# h-bridge-gate-driver-buk.net
KiCad netlist of a schematic drawn in EAGLE
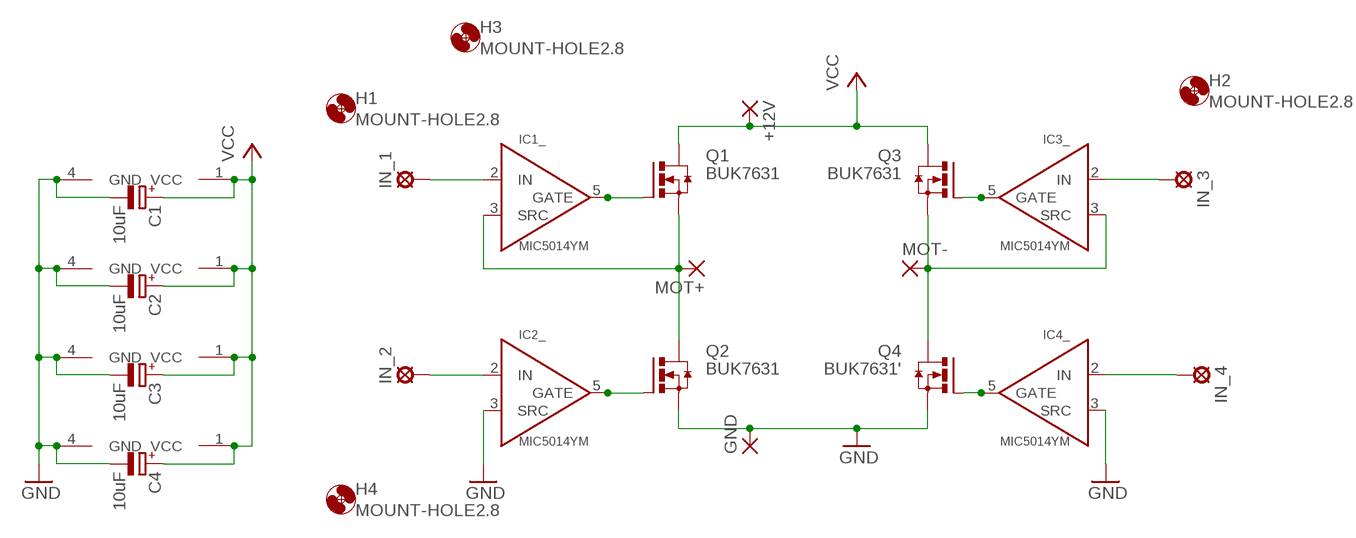
[diagram p0: schematic, sheet 1]

(export (version "E")
  (design (tool "Eeschema 10.0.6"))
  (components
    (comp (ref "+12V")
      (value "WIREPAD4,16O1,6")
      (footprint "eagle-import:4,16O1,6")
      (libsource (lib "eagle-import") (part "WIREPAD4,16O1,6"))
    )
    (comp (ref "C1")
      (value "10uF")
      (footprint "eagle-import:UD-4X5,8_NICHICON")
      (libsource (lib "eagle-import") (part "CPOL-EUUD-4X5,8"))
    )
    (comp (ref "C2")
      (value "10uF")
      (footprint "eagle-import:UD-4X5,8_NICHICON")
      (libsource (lib "eagle-import") (part "CPOL-EUUD-4X5,8"))
    )
    (comp (ref "C3")
      (value "10uF")
      (footprint "eagle-import:UD-4X5,8_NICHICON")
      (libsource (lib "eagle-import") (part "CPOL-EUUD-4X5,8"))
    )
    (comp (ref "C4")
      (value "10uF")
      (footprint "eagle-import:UD-4X5,8_NICHICON")
      (libsource (lib "eagle-import") (part "CPOL-EUUD-4X5,8"))
    )
    (comp (ref "GND")
      (value "WIREPAD4,16O1,6")
      (footprint "eagle-import:4,16O1,6")
      (libsource (lib "eagle-import") (part "WIREPAD4,16O1,6"))
    )
    (comp (ref "H1")
      (value "MOUNT-HOLE2.8")
      (footprint "eagle-import:2,8")
      (libsource (lib "eagle-import") (part "MOUNT-HOLE2.8"))
    )
    (comp (ref "H2")
      (value "MOUNT-HOLE2.8")
      (footprint "eagle-import:2,8")
      (libsource (lib "eagle-import") (part "MOUNT-HOLE2.8"))
    )
    (comp (ref "H3")
      (value "MOUNT-HOLE2.8")
      (footprint "eagle-import:2,8")
      (libsource (lib "eagle-import") (part "MOUNT-HOLE2.8"))
    )
    (comp (ref "H4")
      (value "MOUNT-HOLE2.8")
      (footprint "eagle-import:2,8")
      (libsource (lib "eagle-import") (part "MOUNT-HOLE2.8"))
    )
    (comp (ref "IC1")
      (value "MIC5014YM")
      (footprint "eagle-import:SO8")
      (libsource (lib "eagle-import") (part "MIC5014YM"))
    )
    (comp (ref "IC2")
      (value "MIC5014YM")
      (footprint "eagle-import:SO8")
      (libsource (lib "eagle-import") (part "MIC5014YM"))
    )
    (comp (ref "IC3")
      (value "MIC5014YM")
      (footprint "eagle-import:SO8")
      (libsource (lib "eagle-import") (part "MIC5014YM"))
    )
    (comp (ref "IC4")
      (value "MIC5014YM")
      (footprint "eagle-import:SO8")
      (libsource (lib "eagle-import") (part "MIC5014YM"))
    )
    (comp (ref "IN_1")
      (value "LSP11")
      (footprint "eagle-import:LSP11")
      (libsource (lib "eagle-import") (part "LSP11"))
    )
    (comp (ref "IN_2")
      (value "LSP11")
      (footprint "eagle-import:LSP11")
      (libsource (lib "eagle-import") (part "LSP11"))
    )
    (comp (ref "IN_3")
      (value "LSP11")
      (footprint "eagle-import:LSP11")
      (libsource (lib "eagle-import") (part "LSP11"))
    )
    (comp (ref "IN_4")
      (value "LSP11")
      (footprint "eagle-import:LSP11")
      (libsource (lib "eagle-import") (part "LSP11"))
    )
    (comp (ref "MOT+")
      (value "WIREPAD4,16O1,6")
      (footprint "eagle-import:4,16O1,6")
      (libsource (lib "eagle-import") (part "WIREPAD4,16O1,6"))
    )
    (comp (ref "MOT-")
      (value "WIREPAD4,16O1,6")
      (footprint "eagle-import:4,16O1,6")
      (libsource (lib "eagle-import") (part "WIREPAD4,16O1,6"))
    )
    (comp (ref "Q1")
      (value "BUK7631")
      (footprint "eagle-import:D2PAK_TO263")
      (libsource (lib "eagle-import") (part "BUK7631-100EBUK7631-100E"))
    )
    (comp (ref "Q2")
      (value "BUK7631")
      (footprint "eagle-import:D2PAK_TO263")
      (libsource (lib "eagle-import") (part "BUK7631-100EBUK7631-100E"))
    )
    (comp (ref "Q3")
      (value "BUK7631")
      (footprint "eagle-import:D2PAK_TO263")
      (libsource (lib "eagle-import") (part "BUK7631-100EBUK7631-100E"))
    )
    (comp (ref "Q4")
      (value "BUK7631'")
      (footprint "eagle-import:D2PAK_TO263")
      (libsource (lib "eagle-import") (part "BUK7631-100EBUK7631-100E"))
    )
  )
  (nets
    (net (code "1") (name "GND") (class "Default")
      (node (ref "C1") (pin "-") (pinfunction "-_-") (pintype "passive"))
      (node (ref "C2") (pin "-") (pinfunction "-_-") (pintype "passive"))
      (node (ref "C3") (pin "-") (pinfunction "-_-") (pintype "passive"))
      (node (ref "C4") (pin "-") (pinfunction "-_-") (pintype "passive"))
      (node (ref "GND") (pin "1") (pinfunction "P_1") (pintype "passive"))
      (node (ref "IC1") (pin "4") (pinfunction "GND_4") (pintype "power_in"))
      (node (ref "IC2") (pin "3") (pinfunction "SRC_3") (pintype "passive"))
      (node (ref "IC2") (pin "4") (pinfunction "GND_4") (pintype "power_in"))
      (node (ref "IC3") (pin "4") (pinfunction "GND_4") (pintype "power_in"))
      (node (ref "IC4") (pin "3") (pinfunction "SRC_3") (pintype "passive"))
      (node (ref "IC4") (pin "4") (pinfunction "GND_4") (pintype "power_in"))
      (node (ref "Q2") (pin "3") (pinfunction "S_3") (pintype "passive"))
      (node (ref "Q4") (pin "3") (pinfunction "S_3") (pintype "passive"))
    )
    (net (code "2") (name "Net-(IC1B-GATE)") (class "Default")
      (node (ref "IC1") (pin "5") (pinfunction "GATE_5") (pintype "passive"))
      (node (ref "Q1") (pin "1") (pinfunction "G_1") (pintype "passive"))
    )
    (net (code "3") (name "Net-(IC1B-IN)") (class "Default")
      (node (ref "IC1") (pin "2") (pinfunction "IN_2") (pintype "passive"))
      (node (ref "IN_1") (pin "MP") (pinfunction "MP_MP") (pintype "passive"))
    )
    (net (code "4") (name "Net-(IC1B-SRC)") (class "Default")
      (node (ref "IC1") (pin "3") (pinfunction "SRC_3") (pintype "passive"))
      (node (ref "MOT+") (pin "1") (pinfunction "P_1") (pintype "passive"))
      (node (ref "Q1") (pin "3") (pinfunction "S_3") (pintype "passive"))
      (node (ref "Q2") (pin "4") (pinfunction "D_4") (pintype "passive"))
    )
    (net (code "5") (name "Net-(IC2B-GATE)") (class "Default")
      (node (ref "IC2") (pin "5") (pinfunction "GATE_5") (pintype "passive"))
      (node (ref "Q2") (pin "1") (pinfunction "G_1") (pintype "passive"))
    )
    (net (code "6") (name "Net-(IC2B-IN)") (class "Default")
      (node (ref "IC2") (pin "2") (pinfunction "IN_2") (pintype "passive"))
      (node (ref "IN_2") (pin "MP") (pinfunction "MP_MP") (pintype "passive"))
    )
    (net (code "7") (name "Net-(IC3B-GATE)") (class "Default")
      (node (ref "IC3") (pin "5") (pinfunction "GATE_5") (pintype "passive"))
      (node (ref "Q3") (pin "1") (pinfunction "G_1") (pintype "passive"))
    )
    (net (code "8") (name "Net-(IC3B-IN)") (class "Default")
      (node (ref "IC3") (pin "2") (pinfunction "IN_2") (pintype "passive"))
      (node (ref "IN_3") (pin "MP") (pinfunction "MP_MP") (pintype "passive"))
    )
    (net (code "9") (name "Net-(IC3B-SRC)") (class "Default")
      (node (ref "IC3") (pin "3") (pinfunction "SRC_3") (pintype "passive"))
      (node (ref "MOT-") (pin "1") (pinfunction "P_1") (pintype "passive"))
      (node (ref "Q3") (pin "3") (pinfunction "S_3") (pintype "passive"))
      (node (ref "Q4") (pin "4") (pinfunction "D_4") (pintype "passive"))
    )
    (net (code "10") (name "Net-(IC4B-GATE)") (class "Default")
      (node (ref "IC4") (pin "5") (pinfunction "GATE_5") (pintype "passive"))
      (node (ref "Q4") (pin "1") (pinfunction "G_1") (pintype "passive"))
    )
    (net (code "11") (name "Net-(IC4B-IN)") (class "Default")
      (node (ref "IC4") (pin "2") (pinfunction "IN_2") (pintype "passive"))
      (node (ref "IN_4") (pin "MP") (pinfunction "MP_MP") (pintype "passive"))
    )
    (net (code "12") (name "VCC") (class "Default")
      (node (ref "+12V") (pin "1") (pinfunction "P_1") (pintype "passive"))
      (node (ref "C1") (pin "+") (pinfunction "+_+") (pintype "passive"))
      (node (ref "C2") (pin "+") (pinfunction "+_+") (pintype "passive"))
      (node (ref "C3") (pin "+") (pinfunction "+_+") (pintype "passive"))
      (node (ref "C4") (pin "+") (pinfunction "+_+") (pintype "passive"))
      (node (ref "IC1") (pin "1") (pinfunction "VCC_1") (pintype "power_in"))
      (node (ref "IC2") (pin "1") (pinfunction "VCC_1") (pintype "power_in"))
      (node (ref "IC3") (pin "1") (pinfunction "VCC_1") (pintype "power_in"))
      (node (ref "IC4") (pin "1") (pinfunction "VCC_1") (pintype "power_in"))
      (node (ref "Q1") (pin "4") (pinfunction "D_4") (pintype "passive"))
      (node (ref "Q3") (pin "4") (pinfunction "D_4") (pintype "passive"))
    )
  )
)
